# watchclock.net
KiCad netlist of a schematic drawn in EAGLE
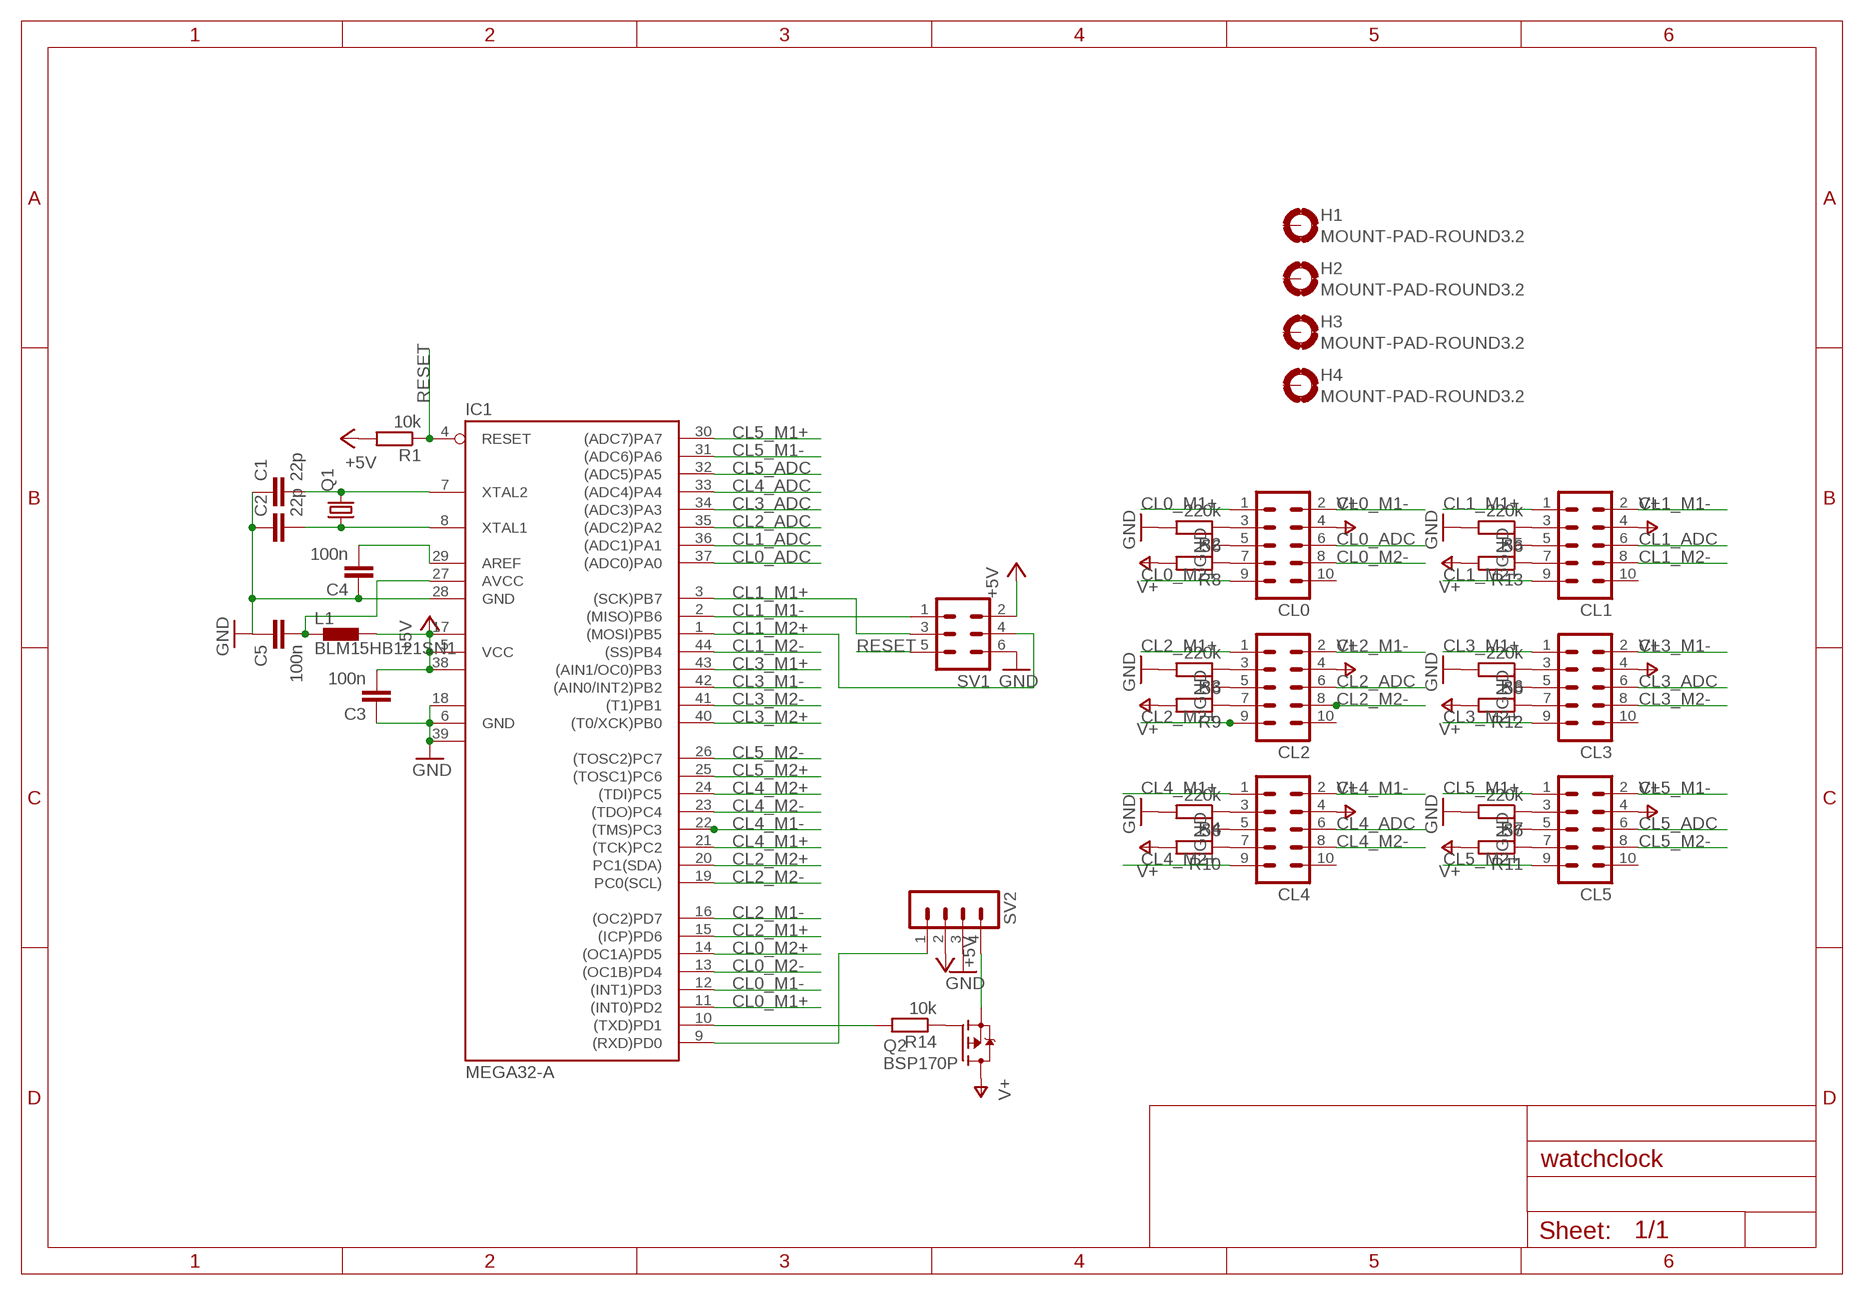
[diagram p0: schematic, sheet 1]

(export (version "E")
  (design (tool "Eeschema 10.0.6"))
  (components
    (comp (ref "C1")
      (value "22p")
      (footprint "eagle-import:C0805")
      (libsource (lib "eagle-import") (part "C-EUC0805"))
    )
    (comp (ref "C2")
      (value "22p")
      (footprint "eagle-import:C0805")
      (libsource (lib "eagle-import") (part "C-EUC0805"))
    )
    (comp (ref "C3")
      (value "100n")
      (footprint "eagle-import:C0805")
      (libsource (lib "eagle-import") (part "C-EUC0805"))
    )
    (comp (ref "C4")
      (value "100n")
      (footprint "eagle-import:C0805")
      (libsource (lib "eagle-import") (part "C-EUC0805"))
    )
    (comp (ref "C5")
      (value "100n")
      (footprint "eagle-import:C0805")
      (libsource (lib "eagle-import") (part "C-EUC0805"))
    )
    (comp (ref "CL0")
      (value "ML10")
      (footprint "eagle-import:ML10")
      (libsource (lib "eagle-import") (part "ML10"))
    )
    (comp (ref "CL1")
      (value "ML10")
      (footprint "eagle-import:ML10")
      (libsource (lib "eagle-import") (part "ML10"))
    )
    (comp (ref "CL2")
      (value "ML10")
      (footprint "eagle-import:ML10")
      (libsource (lib "eagle-import") (part "ML10"))
    )
    (comp (ref "CL3")
      (value "ML10")
      (footprint "eagle-import:ML10")
      (libsource (lib "eagle-import") (part "ML10"))
    )
    (comp (ref "CL4")
      (value "ML10")
      (footprint "eagle-import:ML10")
      (libsource (lib "eagle-import") (part "ML10"))
    )
    (comp (ref "CL5")
      (value "ML10")
      (footprint "eagle-import:ML10")
      (libsource (lib "eagle-import") (part "ML10"))
    )
    (comp (ref "H1")
      (value "MOUNT-PAD-ROUND3.2")
      (footprint "eagle-import:3,2-PAD")
      (libsource (lib "eagle-import") (part "MOUNT-PAD-ROUND3.2"))
    )
    (comp (ref "H2")
      (value "MOUNT-PAD-ROUND3.2")
      (footprint "eagle-import:3,2-PAD")
      (libsource (lib "eagle-import") (part "MOUNT-PAD-ROUND3.2"))
    )
    (comp (ref "H3")
      (value "MOUNT-PAD-ROUND3.2")
      (footprint "eagle-import:3,2-PAD")
      (libsource (lib "eagle-import") (part "MOUNT-PAD-ROUND3.2"))
    )
    (comp (ref "H4")
      (value "MOUNT-PAD-ROUND3.2")
      (footprint "eagle-import:3,2-PAD")
      (libsource (lib "eagle-import") (part "MOUNT-PAD-ROUND3.2"))
    )
    (comp (ref "IC1")
      (value "MEGA32-A")
      (footprint "eagle-import:TQFP44")
      (fields (field (name "MPN") "ATMEGA32-16AU"))
      (libsource (lib "eagle-import") (part "MEGA32-A"))
    )
    (comp (ref "L1")
      (value "BLM15HB121SN1")
      (footprint "eagle-import:0402")
      (libsource (lib "eagle-import") (part "BLM15HB121SN1"))
    )
    (comp (ref "Q1")
      (value "CRYSTALHC49S")
      (footprint "eagle-import:HC49_S")
      (libsource (lib "eagle-import") (part "CRYSTALHC49S"))
    )
    (comp (ref "Q2")
      (value "BSP170P")
      (footprint "eagle-import:SOT223")
      (libsource (lib "eagle-import") (part "BSP170P"))
    )
    (comp (ref "R1")
      (value "10k")
      (footprint "eagle-import:M0805")
      (libsource (lib "eagle-import") (part "R-EU_M0805"))
    )
    (comp (ref "R2")
      (value "220k")
      (footprint "eagle-import:M0805")
      (libsource (lib "eagle-import") (part "R-EU_M0805"))
    )
    (comp (ref "R3")
      (value "220k")
      (footprint "eagle-import:M0805")
      (libsource (lib "eagle-import") (part "R-EU_M0805"))
    )
    (comp (ref "R4")
      (value "220k")
      (footprint "eagle-import:M0805")
      (libsource (lib "eagle-import") (part "R-EU_M0805"))
    )
    (comp (ref "R5")
      (value "220k")
      (footprint "eagle-import:M0805")
      (libsource (lib "eagle-import") (part "R-EU_M0805"))
    )
    (comp (ref "R6")
      (value "220k")
      (footprint "eagle-import:M0805")
      (libsource (lib "eagle-import") (part "R-EU_M0805"))
    )
    (comp (ref "R7")
      (value "220k")
      (footprint "eagle-import:M0805")
      (libsource (lib "eagle-import") (part "R-EU_M0805"))
    )
    (comp (ref "R8")
      (value "56")
      (footprint "eagle-import:M0805")
      (libsource (lib "eagle-import") (part "R-EU_M0805"))
    )
    (comp (ref "R9")
      (value "56")
      (footprint "eagle-import:M0805")
      (libsource (lib "eagle-import") (part "R-EU_M0805"))
    )
    (comp (ref "R10")
      (value "56")
      (footprint "eagle-import:M0805")
      (libsource (lib "eagle-import") (part "R-EU_M0805"))
    )
    (comp (ref "R11")
      (value "56")
      (footprint "eagle-import:M0805")
      (libsource (lib "eagle-import") (part "R-EU_M0805"))
    )
    (comp (ref "R12")
      (value "56")
      (footprint "eagle-import:M0805")
      (libsource (lib "eagle-import") (part "R-EU_M0805"))
    )
    (comp (ref "R13")
      (value "56")
      (footprint "eagle-import:M0805")
      (libsource (lib "eagle-import") (part "R-EU_M0805"))
    )
    (comp (ref "R14")
      (value "10k")
      (footprint "eagle-import:M0805")
      (libsource (lib "eagle-import") (part "R-EU_M0805"))
    )
    (comp (ref "SV1")
      (value "ML6")
      (footprint "eagle-import:ML6")
      (libsource (lib "eagle-import") (part "ML6"))
    )
    (comp (ref "SV2")
      (value "MA04-1")
      (footprint "eagle-import:MA04-1")
      (libsource (lib "eagle-import") (part "MA04-1"))
    )
  )
  (nets
    (net (code "1") (name "+5V") (class "Default")
      (node (ref "C3") (pin "2") (pinfunction "2_2") (pintype "passive"))
      (node (ref "IC1") (pin "17") (pinfunction "VCC1_17") (pintype "power_in"))
      (node (ref "IC1") (pin "38") (pinfunction "VCC2_38") (pintype "power_in"))
      (node (ref "IC1") (pin "5") (pinfunction "VCC_5") (pintype "power_in"))
      (node (ref "L1") (pin "2") (pinfunction "2_2") (pintype "passive"))
      (node (ref "R1") (pin "2") (pinfunction "2_2") (pintype "passive"))
      (node (ref "SV1") (pin "2") (pinfunction "2_2") (pintype "passive"))
      (node (ref "SV2") (pin "2") (pinfunction "2_2") (pintype "passive"))
    )
    (net (code "2") (name "/CL0_ADC") (class "Default")
      (node (ref "CL0") (pin "6") (pinfunction "6_6") (pintype "passive"))
      (node (ref "IC1") (pin "37") (pinfunction "(ADC0)PA0_37") (pintype "bidirectional"))
    )
    (net (code "3") (name "/CL0_M1+") (class "Default")
      (node (ref "CL0") (pin "1") (pinfunction "1_1") (pintype "passive"))
      (node (ref "IC1") (pin "11") (pinfunction "(INT0)PD2_11") (pintype "bidirectional"))
    )
    (net (code "4") (name "/CL0_M1-") (class "Default")
      (node (ref "CL0") (pin "2") (pinfunction "2_2") (pintype "passive"))
      (node (ref "IC1") (pin "12") (pinfunction "(INT1)PD3_12") (pintype "bidirectional"))
    )
    (net (code "5") (name "/CL0_M2+") (class "Default")
      (node (ref "CL0") (pin "9") (pinfunction "9_9") (pintype "passive"))
      (node (ref "IC1") (pin "14") (pinfunction "(OC1A)PD5_14") (pintype "bidirectional"))
    )
    (net (code "6") (name "/CL0_M2-") (class "Default")
      (node (ref "CL0") (pin "8") (pinfunction "8_8") (pintype "passive"))
      (node (ref "IC1") (pin "13") (pinfunction "(OC1B)PD4_13") (pintype "bidirectional"))
    )
    (net (code "7") (name "/CL1_ADC") (class "Default")
      (node (ref "CL1") (pin "6") (pinfunction "6_6") (pintype "passive"))
      (node (ref "IC1") (pin "36") (pinfunction "(ADC1)PA1_36") (pintype "bidirectional"))
    )
    (net (code "8") (name "/CL1_M1+") (class "Default")
      (node (ref "CL1") (pin "1") (pinfunction "1_1") (pintype "passive"))
      (node (ref "IC1") (pin "3") (pinfunction "(SCK)PB7_3") (pintype "bidirectional"))
      (node (ref "SV1") (pin "3") (pinfunction "3_3") (pintype "passive"))
    )
    (net (code "9") (name "/CL1_M1-") (class "Default")
      (node (ref "CL1") (pin "2") (pinfunction "2_2") (pintype "passive"))
      (node (ref "IC1") (pin "2") (pinfunction "(MISO)PB6_2") (pintype "bidirectional"))
      (node (ref "SV1") (pin "1") (pinfunction "1_1") (pintype "passive"))
    )
    (net (code "10") (name "/CL1_M2+") (class "Default")
      (node (ref "CL1") (pin "9") (pinfunction "9_9") (pintype "passive"))
      (node (ref "IC1") (pin "1") (pinfunction "(MOSI)PB5_1") (pintype "bidirectional"))
      (node (ref "SV1") (pin "4") (pinfunction "4_4") (pintype "passive"))
    )
    (net (code "11") (name "/CL1_M2-") (class "Default")
      (node (ref "CL1") (pin "8") (pinfunction "8_8") (pintype "passive"))
      (node (ref "IC1") (pin "44") (pinfunction "(SS)PB4_44") (pintype "bidirectional"))
    )
    (net (code "12") (name "/CL2_ADC") (class "Default")
      (node (ref "CL2") (pin "6") (pinfunction "6_6") (pintype "passive"))
      (node (ref "IC1") (pin "35") (pinfunction "(ADC2)PA2_35") (pintype "bidirectional"))
    )
    (net (code "13") (name "/CL2_M1+") (class "Default")
      (node (ref "CL2") (pin "1") (pinfunction "1_1") (pintype "passive"))
      (node (ref "IC1") (pin "15") (pinfunction "(ICP)PD6_15") (pintype "bidirectional"))
    )
    (net (code "14") (name "/CL2_M1-") (class "Default")
      (node (ref "CL2") (pin "2") (pinfunction "2_2") (pintype "passive"))
      (node (ref "IC1") (pin "16") (pinfunction "(OC2)PD7_16") (pintype "bidirectional"))
    )
    (net (code "15") (name "/CL2_M2+") (class "Default")
      (node (ref "CL2") (pin "9") (pinfunction "9_9") (pintype "passive"))
      (node (ref "IC1") (pin "20") (pinfunction "PC1(SDA)_20") (pintype "bidirectional"))
    )
    (net (code "16") (name "/CL2_M2-") (class "Default")
      (node (ref "CL2") (pin "8") (pinfunction "8_8") (pintype "passive"))
      (node (ref "IC1") (pin "19") (pinfunction "PC0(SCL)_19") (pintype "bidirectional"))
    )
    (net (code "17") (name "/CL3_ADC") (class "Default")
      (node (ref "CL3") (pin "6") (pinfunction "6_6") (pintype "passive"))
      (node (ref "IC1") (pin "34") (pinfunction "(ADC3)PA3_34") (pintype "bidirectional"))
    )
    (net (code "18") (name "/CL3_M1+") (class "Default")
      (node (ref "CL3") (pin "1") (pinfunction "1_1") (pintype "passive"))
      (node (ref "IC1") (pin "43") (pinfunction "(AIN1/OC0)PB3_43") (pintype "bidirectional"))
    )
    (net (code "19") (name "/CL3_M1-") (class "Default")
      (node (ref "CL3") (pin "2") (pinfunction "2_2") (pintype "passive"))
      (node (ref "IC1") (pin "42") (pinfunction "(AIN0/INT2)PB2_42") (pintype "bidirectional"))
    )
    (net (code "20") (name "/CL3_M2+") (class "Default")
      (node (ref "CL3") (pin "9") (pinfunction "9_9") (pintype "passive"))
      (node (ref "IC1") (pin "40") (pinfunction "(T0/XCK)PB0_40") (pintype "bidirectional"))
    )
    (net (code "21") (name "/CL3_M2-") (class "Default")
      (node (ref "CL3") (pin "8") (pinfunction "8_8") (pintype "passive"))
      (node (ref "IC1") (pin "41") (pinfunction "(T1)PB1_41") (pintype "bidirectional"))
    )
    (net (code "22") (name "/CL4_ADC") (class "Default")
      (node (ref "CL4") (pin "6") (pinfunction "6_6") (pintype "passive"))
      (node (ref "IC1") (pin "33") (pinfunction "(ADC4)PA4_33") (pintype "bidirectional"))
    )
    (net (code "23") (name "/CL4_M1+") (class "Default")
      (node (ref "CL4") (pin "1") (pinfunction "1_1") (pintype "passive"))
      (node (ref "IC1") (pin "21") (pinfunction "(TCK)PC2_21") (pintype "bidirectional"))
    )
    (net (code "24") (name "/CL4_M1-") (class "Default")
      (node (ref "CL4") (pin "2") (pinfunction "2_2") (pintype "passive"))
      (node (ref "IC1") (pin "22") (pinfunction "(TMS)PC3_22") (pintype "bidirectional"))
    )
    (net (code "25") (name "/CL4_M2+") (class "Default")
      (node (ref "CL4") (pin "9") (pinfunction "9_9") (pintype "passive"))
      (node (ref "IC1") (pin "24") (pinfunction "(TDI)PC5_24") (pintype "bidirectional"))
    )
    (net (code "26") (name "/CL4_M2-") (class "Default")
      (node (ref "CL4") (pin "8") (pinfunction "8_8") (pintype "passive"))
      (node (ref "IC1") (pin "23") (pinfunction "(TDO)PC4_23") (pintype "bidirectional"))
    )
    (net (code "27") (name "/CL5_ADC") (class "Default")
      (node (ref "CL5") (pin "6") (pinfunction "6_6") (pintype "passive"))
      (node (ref "IC1") (pin "32") (pinfunction "(ADC5)PA5_32") (pintype "bidirectional"))
    )
    (net (code "28") (name "/CL5_M1+") (class "Default")
      (node (ref "CL5") (pin "1") (pinfunction "1_1") (pintype "passive"))
      (node (ref "IC1") (pin "30") (pinfunction "(ADC7)PA7_30") (pintype "bidirectional"))
    )
    (net (code "29") (name "/CL5_M1-") (class "Default")
      (node (ref "CL5") (pin "2") (pinfunction "2_2") (pintype "passive"))
      (node (ref "IC1") (pin "31") (pinfunction "(ADC6)PA6_31") (pintype "bidirectional"))
    )
    (net (code "30") (name "/CL5_M2+") (class "Default")
      (node (ref "CL5") (pin "9") (pinfunction "9_9") (pintype "passive"))
      (node (ref "IC1") (pin "25") (pinfunction "(TOSC1)PC6_25") (pintype "bidirectional"))
    )
    (net (code "31") (name "/CL5_M2-") (class "Default")
      (node (ref "CL5") (pin "8") (pinfunction "8_8") (pintype "passive"))
      (node (ref "IC1") (pin "26") (pinfunction "(TOSC2)PC7_26") (pintype "bidirectional"))
    )
    (net (code "32") (name "/RESET") (class "Default")
      (node (ref "IC1") (pin "4") (pinfunction "RESET_4") (pintype "input"))
      (node (ref "R1") (pin "1") (pinfunction "1_1") (pintype "passive"))
      (node (ref "SV1") (pin "5") (pinfunction "5_5") (pintype "passive"))
    )
    (net (code "33") (name "GND") (class "Default")
      (node (ref "C1") (pin "1") (pinfunction "1_1") (pintype "passive"))
      (node (ref "C2") (pin "1") (pinfunction "1_1") (pintype "passive"))
      (node (ref "C3") (pin "1") (pinfunction "1_1") (pintype "passive"))
      (node (ref "C4") (pin "1") (pinfunction "1_1") (pintype "passive"))
      (node (ref "C5") (pin "1") (pinfunction "1_1") (pintype "passive"))
      (node (ref "CL0") (pin "5") (pinfunction "5_5") (pintype "passive"))
      (node (ref "CL1") (pin "5") (pinfunction "5_5") (pintype "passive"))
      (node (ref "CL2") (pin "5") (pinfunction "5_5") (pintype "passive"))
      (node (ref "CL3") (pin "5") (pinfunction "5_5") (pintype "passive"))
      (node (ref "CL4") (pin "5") (pinfunction "5_5") (pintype "passive"))
      (node (ref "CL5") (pin "5") (pinfunction "5_5") (pintype "passive"))
      (node (ref "IC1") (pin "18") (pinfunction "GND1_18") (pintype "power_in"))
      (node (ref "IC1") (pin "28") (pinfunction "GND_28") (pintype "power_in"))
      (node (ref "IC1") (pin "39") (pinfunction "GND2_39") (pintype "power_in"))
      (node (ref "IC1") (pin "6") (pinfunction "GND_6") (pintype "power_in"))
      (node (ref "R2") (pin "2") (pinfunction "2_2") (pintype "passive"))
      (node (ref "R3") (pin "2") (pinfunction "2_2") (pintype "passive"))
      (node (ref "R4") (pin "2") (pinfunction "2_2") (pintype "passive"))
      (node (ref "R5") (pin "2") (pinfunction "2_2") (pintype "passive"))
      (node (ref "R6") (pin "2") (pinfunction "2_2") (pintype "passive"))
      (node (ref "R7") (pin "2") (pinfunction "2_2") (pintype "passive"))
      (node (ref "SV1") (pin "6") (pinfunction "6_6") (pintype "passive"))
      (node (ref "SV2") (pin "3") (pinfunction "3_3") (pintype "passive"))
    )
    (net (code "34") (name "Net-(CL0-Pad3)") (class "Default")
      (node (ref "CL0") (pin "3") (pinfunction "3_3") (pintype "passive"))
      (node (ref "R2") (pin "1") (pinfunction "1_1") (pintype "passive"))
    )
    (net (code "35") (name "Net-(CL0-Pad7)") (class "Default")
      (node (ref "CL0") (pin "7") (pinfunction "7_7") (pintype "passive"))
      (node (ref "R8") (pin "1") (pinfunction "1_1") (pintype "passive"))
    )
    (net (code "36") (name "Net-(CL1-Pad3)") (class "Default")
      (node (ref "CL1") (pin "3") (pinfunction "3_3") (pintype "passive"))
      (node (ref "R5") (pin "1") (pinfunction "1_1") (pintype "passive"))
    )
    (net (code "37") (name "Net-(CL1-Pad7)") (class "Default")
      (node (ref "CL1") (pin "7") (pinfunction "7_7") (pintype "passive"))
      (node (ref "R13") (pin "1") (pinfunction "1_1") (pintype "passive"))
    )
    (net (code "38") (name "Net-(CL2-Pad3)") (class "Default")
      (node (ref "CL2") (pin "3") (pinfunction "3_3") (pintype "passive"))
      (node (ref "R3") (pin "1") (pinfunction "1_1") (pintype "passive"))
    )
    (net (code "39") (name "Net-(CL2-Pad7)") (class "Default")
      (node (ref "CL2") (pin "7") (pinfunction "7_7") (pintype "passive"))
      (node (ref "R9") (pin "1") (pinfunction "1_1") (pintype "passive"))
    )
    (net (code "40") (name "Net-(CL3-Pad3)") (class "Default")
      (node (ref "CL3") (pin "3") (pinfunction "3_3") (pintype "passive"))
      (node (ref "R6") (pin "1") (pinfunction "1_1") (pintype "passive"))
    )
    (net (code "41") (name "Net-(CL3-Pad7)") (class "Default")
      (node (ref "CL3") (pin "7") (pinfunction "7_7") (pintype "passive"))
      (node (ref "R12") (pin "1") (pinfunction "1_1") (pintype "passive"))
    )
    (net (code "42") (name "Net-(CL4-Pad3)") (class "Default")
      (node (ref "CL4") (pin "3") (pinfunction "3_3") (pintype "passive"))
      (node (ref "R4") (pin "1") (pinfunction "1_1") (pintype "passive"))
    )
    (net (code "43") (name "Net-(CL4-Pad7)") (class "Default")
      (node (ref "CL4") (pin "7") (pinfunction "7_7") (pintype "passive"))
      (node (ref "R10") (pin "1") (pinfunction "1_1") (pintype "passive"))
    )
    (net (code "44") (name "Net-(CL5-Pad3)") (class "Default")
      (node (ref "CL5") (pin "3") (pinfunction "3_3") (pintype "passive"))
      (node (ref "R7") (pin "1") (pinfunction "1_1") (pintype "passive"))
    )
    (net (code "45") (name "Net-(CL5-Pad7)") (class "Default")
      (node (ref "CL5") (pin "7") (pinfunction "7_7") (pintype "passive"))
      (node (ref "R11") (pin "1") (pinfunction "1_1") (pintype "passive"))
    )
    (net (code "46") (name "Net-(IC1-(RXD)PD0)") (class "Default")
      (node (ref "IC1") (pin "9") (pinfunction "(RXD)PD0_9") (pintype "bidirectional"))
      (node (ref "SV2") (pin "1") (pinfunction "1_1") (pintype "passive"))
    )
    (net (code "47") (name "Net-(IC1-(TXD)PD1)") (class "Default")
      (node (ref "IC1") (pin "10") (pinfunction "(TXD)PD1_10") (pintype "bidirectional"))
      (node (ref "R14") (pin "2") (pinfunction "2_2") (pintype "passive"))
    )
    (net (code "48") (name "Net-(IC1-AREF)") (class "Default")
      (node (ref "C4") (pin "2") (pinfunction "2_2") (pintype "passive"))
      (node (ref "IC1") (pin "29") (pinfunction "AREF_29") (pintype "passive"))
    )
    (net (code "49") (name "Net-(IC1-AVCC)") (class "Default")
      (node (ref "C5") (pin "2") (pinfunction "2_2") (pintype "passive"))
      (node (ref "IC1") (pin "27") (pinfunction "AVCC_27") (pintype "power_in"))
      (node (ref "L1") (pin "1") (pinfunction "1_1") (pintype "passive"))
    )
    (net (code "50") (name "Net-(IC1-XTAL1)") (class "Default")
      (node (ref "C2") (pin "2") (pinfunction "2_2") (pintype "passive"))
      (node (ref "IC1") (pin "8") (pinfunction "XTAL1_8") (pintype "bidirectional"))
      (node (ref "Q1") (pin "1") (pinfunction "1_1") (pintype "passive"))
    )
    (net (code "51") (name "Net-(IC1-XTAL2)") (class "Default")
      (node (ref "C1") (pin "2") (pinfunction "2_2") (pintype "passive"))
      (node (ref "IC1") (pin "7") (pinfunction "XTAL2_7") (pintype "bidirectional"))
      (node (ref "Q1") (pin "2") (pinfunction "2_2") (pintype "passive"))
    )
    (net (code "52") (name "Net-(Q2-G)") (class "Default")
      (node (ref "Q2") (pin "1") (pinfunction "G_1") (pintype "passive"))
      (node (ref "R14") (pin "1") (pinfunction "1_1") (pintype "passive"))
    )
    (net (code "53") (name "Net-(Q2-S)") (class "Default")
      (node (ref "Q2") (pin "3") (pinfunction "S_3") (pintype "passive"))
      (node (ref "SV2") (pin "4") (pinfunction "4_4") (pintype "passive"))
    )
    (net (code "54") (name "V+") (class "Default")
      (node (ref "CL0") (pin "4") (pinfunction "4_4") (pintype "passive"))
      (node (ref "CL1") (pin "4") (pinfunction "4_4") (pintype "passive"))
      (node (ref "CL2") (pin "4") (pinfunction "4_4") (pintype "passive"))
      (node (ref "CL3") (pin "4") (pinfunction "4_4") (pintype "passive"))
      (node (ref "CL4") (pin "4") (pinfunction "4_4") (pintype "passive"))
      (node (ref "CL5") (pin "4") (pinfunction "4_4") (pintype "passive"))
      (node (ref "Q2") (pin "2") (pinfunction "D_2") (pintype "passive"))
      (node (ref "Q2") (pin "4") (pinfunction "D_4") (pintype "passive"))
      (node (ref "R10") (pin "2") (pinfunction "2_2") (pintype "passive"))
      (node (ref "R11") (pin "2") (pinfunction "2_2") (pintype "passive"))
      (node (ref "R12") (pin "2") (pinfunction "2_2") (pintype "passive"))
      (node (ref "R13") (pin "2") (pinfunction "2_2") (pintype "passive"))
      (node (ref "R8") (pin "2") (pinfunction "2_2") (pintype "passive"))
      (node (ref "R9") (pin "2") (pinfunction "2_2") (pintype "passive"))
    )
    (net (code "55") (name "unconnected-(CL0-Pad10)") (class "Default")
      (node (ref "CL0") (pin "10") (pinfunction "10_10") (pintype "passive"))
    )
    (net (code "56") (name "unconnected-(CL1-Pad10)") (class "Default")
      (node (ref "CL1") (pin "10") (pinfunction "10_10") (pintype "passive"))
    )
    (net (code "57") (name "unconnected-(CL2-Pad10)") (class "Default")
      (node (ref "CL2") (pin "10") (pinfunction "10_10") (pintype "passive"))
    )
    (net (code "58") (name "unconnected-(CL3-Pad10)") (class "Default")
      (node (ref "CL3") (pin "10") (pinfunction "10_10") (pintype "passive"))
    )
    (net (code "59") (name "unconnected-(CL4-Pad10)") (class "Default")
      (node (ref "CL4") (pin "10") (pinfunction "10_10") (pintype "passive"))
    )
    (net (code "60") (name "unconnected-(CL5-Pad10)") (class "Default")
      (node (ref "CL5") (pin "10") (pinfunction "10_10") (pintype "passive"))
    )
    (net (code "61") (name "unconnected-(H1-MOUNT-PadB3,2)") (class "Default")
      (node (ref "H1") (pin "B3,2") (pinfunction "MOUNT_B3,2") (pintype "passive"))
    )
    (net (code "62") (name "unconnected-(H2-MOUNT-PadB3,2)") (class "Default")
      (node (ref "H2") (pin "B3,2") (pinfunction "MOUNT_B3,2") (pintype "passive"))
    )
    (net (code "63") (name "unconnected-(H3-MOUNT-PadB3,2)") (class "Default")
      (node (ref "H3") (pin "B3,2") (pinfunction "MOUNT_B3,2") (pintype "passive"))
    )
    (net (code "64") (name "unconnected-(H4-MOUNT-PadB3,2)") (class "Default")
      (node (ref "H4") (pin "B3,2") (pinfunction "MOUNT_B3,2") (pintype "passive"))
    )
  )
)
